# SCH_nfc_card_2024-04-11.net
KiCad netlist of a schematic drawn in EasyEDA
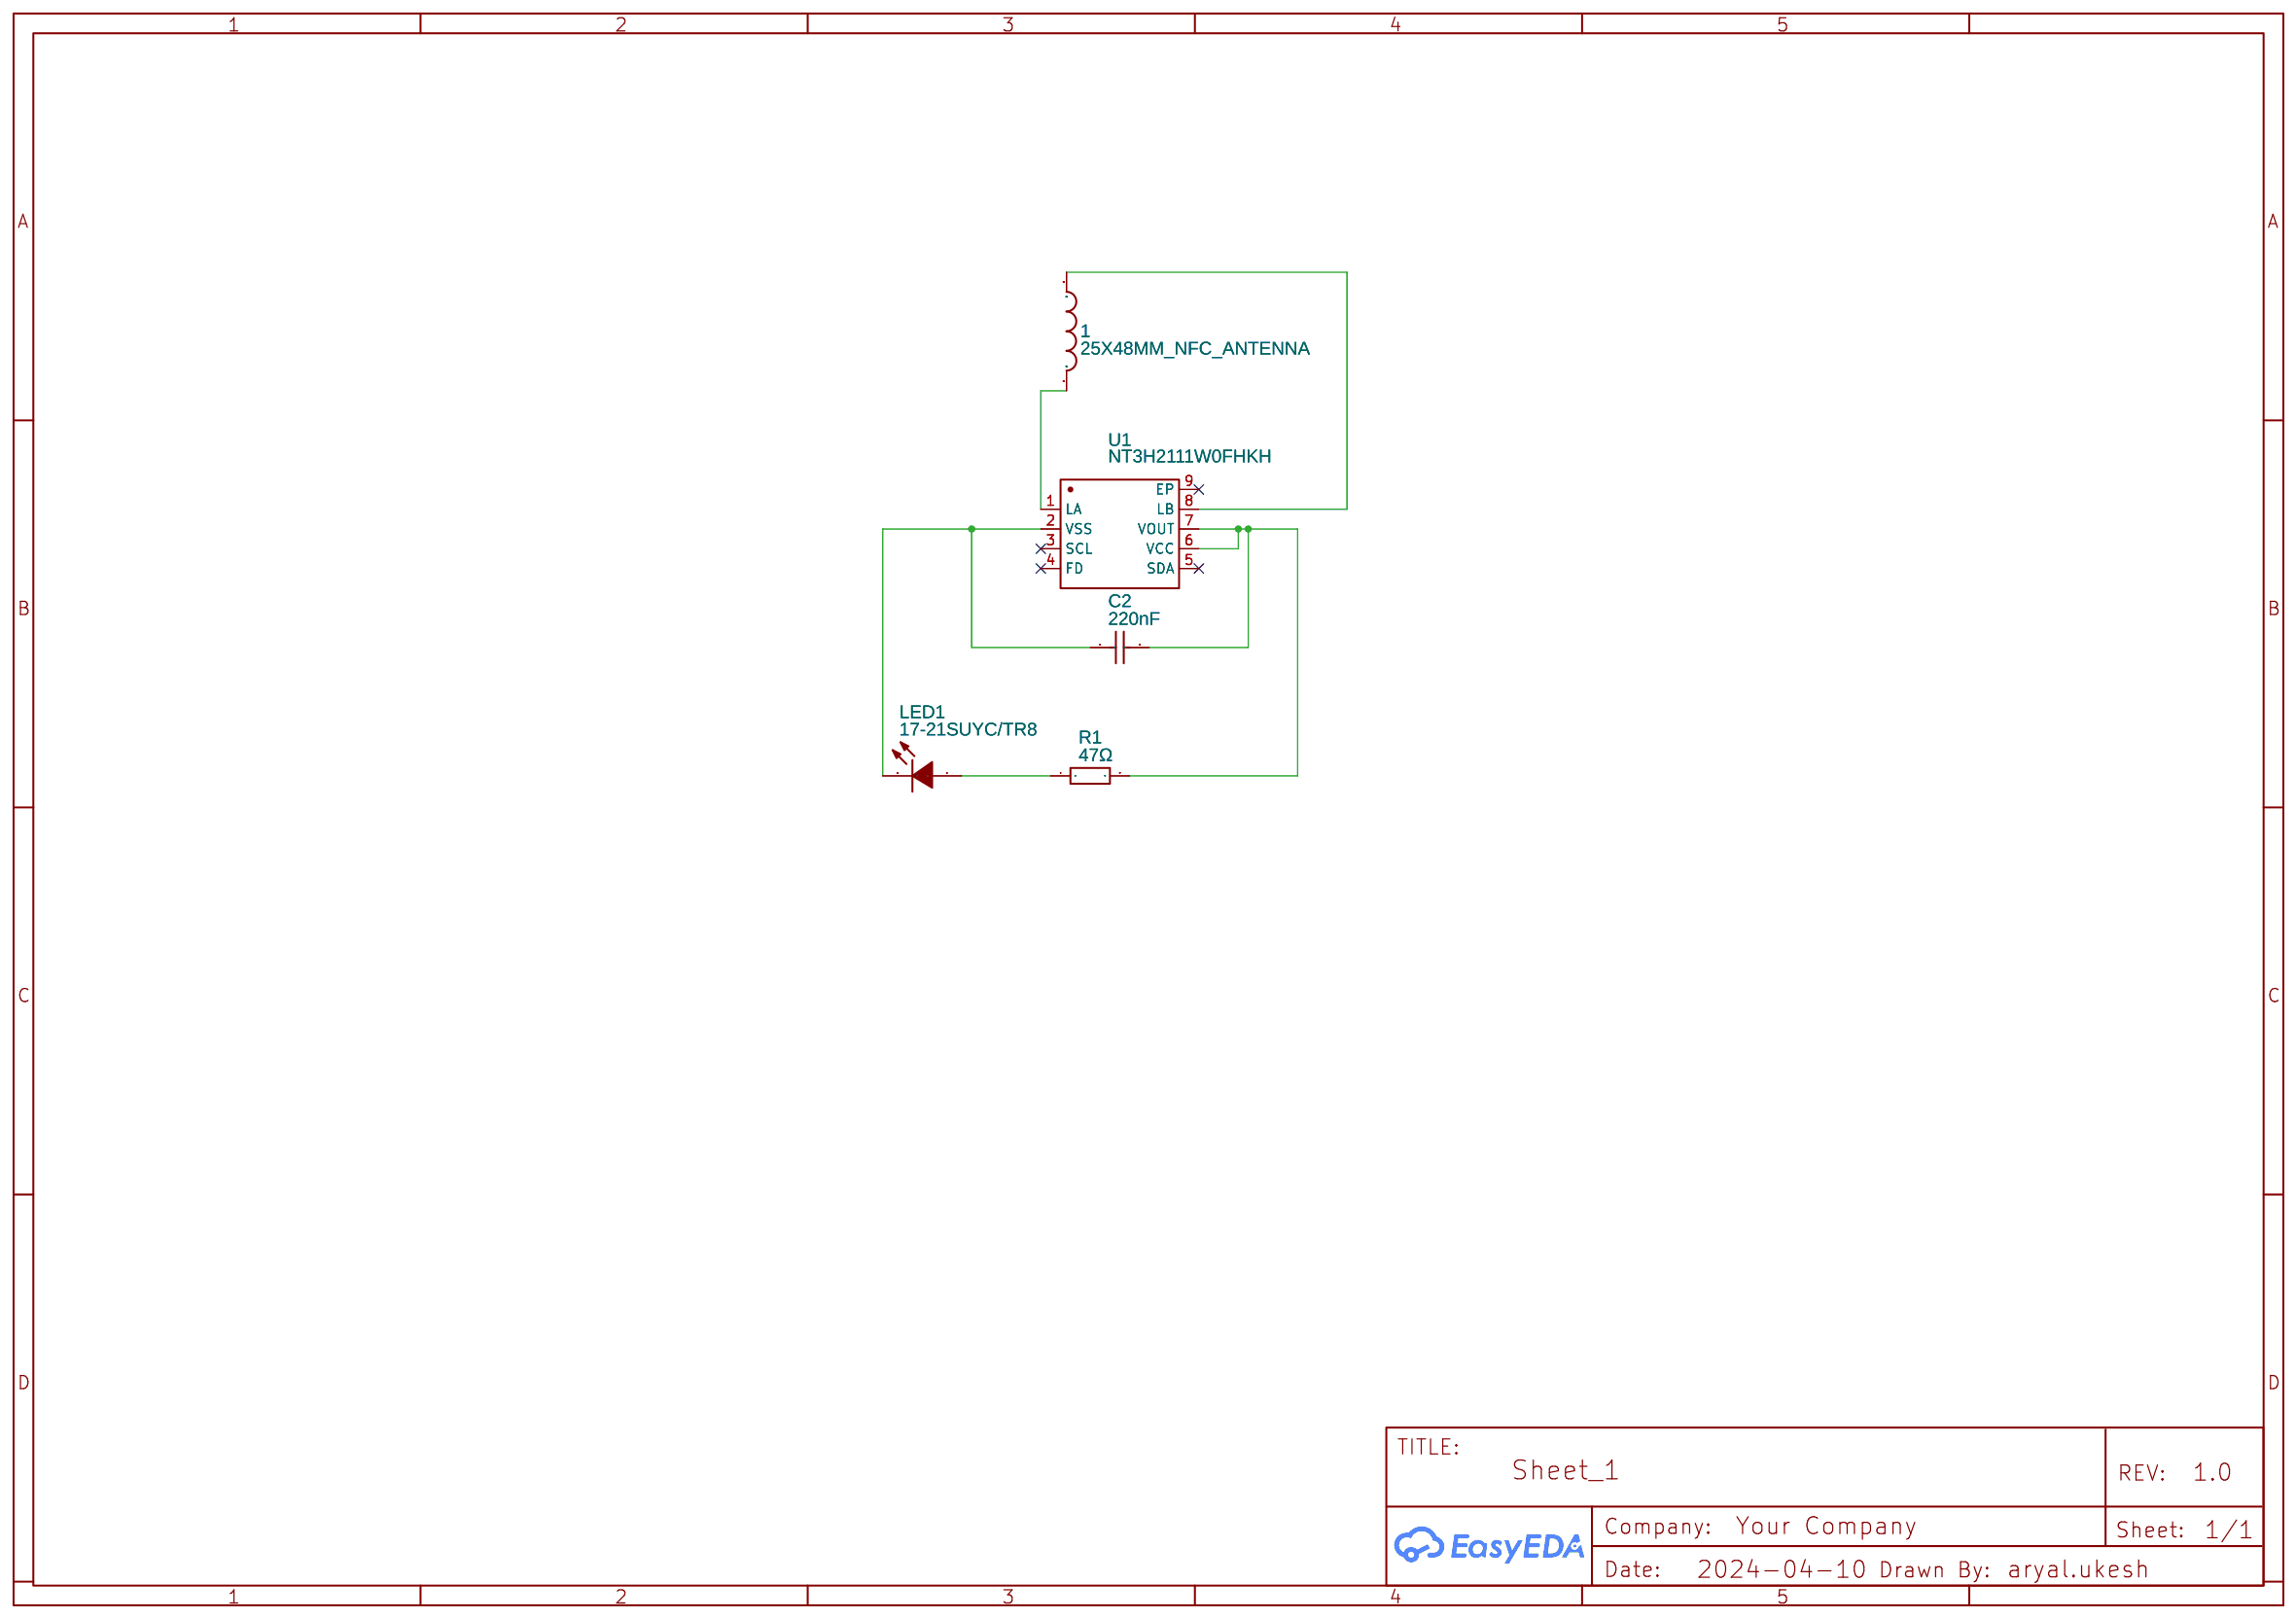
[diagram p0: schematic sheet]

(export (version "E")
  (design (tool "Eeschema 10.0.6"))
  (components
    (comp (ref "1") (value "25X48MM_NFC_ANTENNA") (libsource (lib "") (part "25X48MM_NFC_ANTENNA")))
    (comp (ref "C2")
      (value "220nF")
      (fields (field (name "Manufacturer Part") "0805F224Z500CT") (field (name "Manufacturer") "Walsin(华新科)"))
      (libsource (lib "") (part "0805F224Z500"))
    )
    (comp (ref "LED1")
      (value "17-21SUYC/TR8")
      (fields (field (name "Manufacturer Part") "KT-0805黄灯") (field (name "Manufacturer") "KENTO"))
      (libsource (lib "") (part "17-21SUYC/TR8"))
    )
    (comp (ref "R1")
      (value "47Ω")
      (fields
        (field (name "Manufacturer Part") "QR0805F47R0P05Z")
        (field (name "Manufacturer") "EVER OHMS(天二科技)")
      )
      (libsource (lib "") (part "QR0805F47RP05"))
    )
    (comp (ref "U1")
      (value "NT3H2111W0FHKH")
      (fields (field (name "Manufacturer") "NXP(恩智浦)"))
      (libsource (lib "") (part "NT3H2111W0FHKH"))
    )
  )
  (nets
    (net (code "1") (name "Net-(LED1-+)") (class "Default")
      (node (ref "LED1") (pin "1") (pinfunction "+_1") (pintype "unspecified"))
      (node (ref "R1") (pin "1") (pinfunction "1_1") (pintype "unspecified"))
    )
    (net (code "2") (name "Net-(LED1--)") (class "Default")
      (node (ref "C2") (pin "1") (pinfunction "1_1") (pintype "input"))
      (node (ref "LED1") (pin "2") (pinfunction "-_2") (pintype "unspecified"))
      (node (ref "U1") (pin "2") (pinfunction "VSS_2") (pintype "unspecified"))
    )
    (net (code "3") (name "Net-(U1-LA)") (class "Default")
      (node (ref "1") (pin "P$2") (pinfunction "P$2_P$2") (pintype "bidirectional"))
      (node (ref "U1") (pin "1") (pinfunction "LA_1") (pintype "unspecified"))
    )
    (net (code "4") (name "Net-(U1-LB)") (class "Default")
      (node (ref "1") (pin "P$1") (pinfunction "P$1_P$1") (pintype "bidirectional"))
      (node (ref "U1") (pin "8") (pinfunction "LB_8") (pintype "unspecified"))
    )
    (net (code "5") (name "Net-(U1-VCC)") (class "Default")
      (node (ref "C2") (pin "2") (pinfunction "2_2") (pintype "input"))
      (node (ref "R1") (pin "2") (pinfunction "2_2") (pintype "unspecified"))
      (node (ref "U1") (pin "6") (pinfunction "VCC_6") (pintype "unspecified"))
      (node (ref "U1") (pin "7") (pinfunction "VOUT_7") (pintype "unspecified"))
    )
    (net (code "6") (name "unconnected-(U1-EP-Pad9)") (class "Default")
      (node (ref "U1") (pin "9") (pinfunction "EP_9") (pintype "unspecified+no_connect"))
    )
    (net (code "7") (name "unconnected-(U1-FD-Pad4)") (class "Default")
      (node (ref "U1") (pin "4") (pinfunction "FD_4") (pintype "unspecified+no_connect"))
    )
    (net (code "8") (name "unconnected-(U1-SCL-Pad3)") (class "Default")
      (node (ref "U1") (pin "3") (pinfunction "SCL_3") (pintype "unspecified+no_connect"))
    )
    (net (code "9") (name "unconnected-(U1-SDA-Pad5)") (class "Default")
      (node (ref "U1") (pin "5") (pinfunction "SDA_5") (pintype "unspecified+no_connect"))
    )
  )
)
